# AdjRegSection.net
KiCad netlist of a schematic drawn in Altium Designer
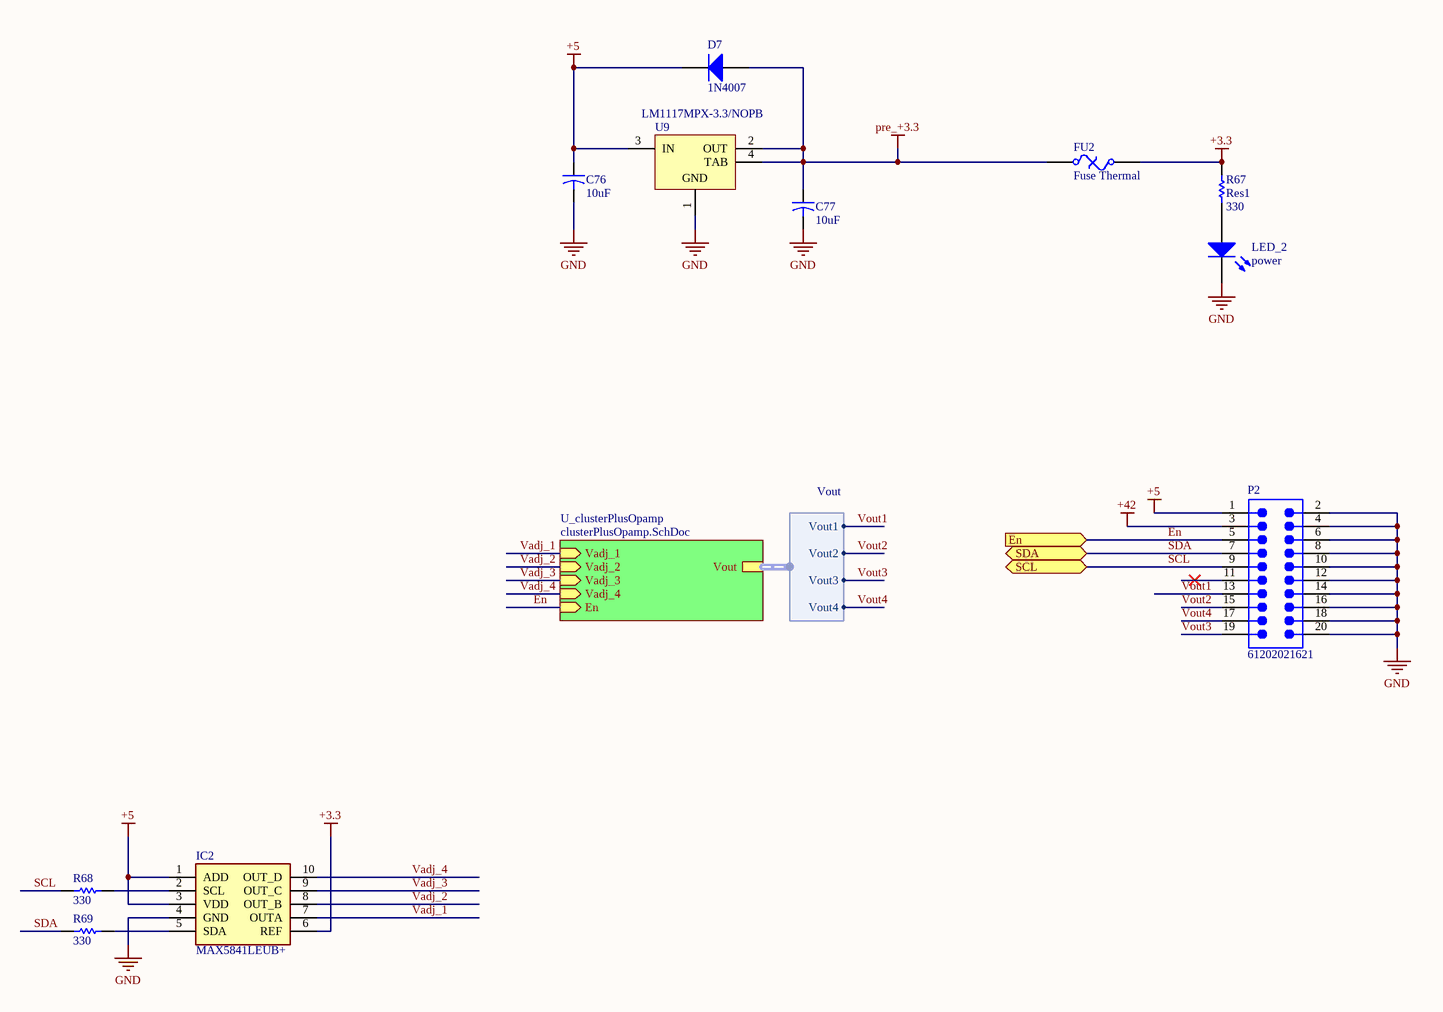
[diagram p0: AdjRegSection.SchDoc]

(export (version "E")
  (design (tool "Eeschema 10.0.6"))
  (components
    (comp (ref "C76")
      (value "10uF")
      (footprint "0805C")
      (description "Capacitor")
      (fields (field (name "Comment") "Cap_El") (field (name "PUBLISHER") "Altium Limited"))
      (libsource (lib "KN2CLib") (part "Cap_El"))
    )
    (comp (ref "C77")
      (value "10uF")
      (footprint "0805C")
      (description "Capacitor")
      (fields (field (name "Comment") "Cap_El") (field (name "PUBLISHER") "Altium Limited"))
      (libsource (lib "KN2CLib") (part "Cap_El"))
    )
    (comp (ref "D7")
      (value "1N4007")
      (footprint "430X270D")
      (description "1 Amp General Purpose Rectifier")
      (fields (field (name "PUBLISHER") "Altium Limited"))
      (libsource (lib "KN2CLib") (part "Diode"))
    )
    (comp (ref "FU2")
      (value "Fuse Thermal")
      (footprint "1206")
      (description "Thermal Fuse")
      (fields (field (name "PUBLISHER") "Altium Limited"))
      (libsource (lib "Miscellaneous Devices") (part "Fuse Thermal"))
    )
    (comp (ref "IC2")
      (value "MAX5841LEUB+")
      (footprint "SamacSys:SOP50P490X110-10N")
      (description "Integrated Circuit")
      (fields (field (name "MOUSER PART NUMBER") "700-MAX5841LEUB"))
      (libsource (lib "*") (part "MAX5841LEUB+"))
    )
    (comp (ref "LED_2")
      (value "power")
      (footprint "0805LED")
      (description "Typical BLUE SiC LED")
      (fields (field (name "PUBLISHER") "Altium Limited"))
      (libsource (lib "Miscellaneous Devices") (part "LED3"))
    )
    (comp (ref "P2")
      (value "61202021621")
      (footprint "61202021621")
      (libsource (lib "Altium Content Vault") (part "Header_Male_2R_20P"))
    )
    (comp (ref "R67")
      (value "Res1")
      (footprint "0805L")
      (description "Resistor")
      (fields (field (name "ALTIUM_VALUE") "330") (field (name "PUBLISHER") "Altium Limited"))
      (libsource (lib "Miscellaneous Devices") (part "Res1"))
    )
    (comp (ref "R68")
      (value "330")
      (footprint "RESC3216X70X50NL05T20")
      (fields (field (name "PART NUMBER") "ERJ8BWFR068V") (field (name "MANUFACTURER") "Panasonic"))
      (libsource (lib "Altium Content Vault") (part "RES"))
    )
    (comp (ref "R69")
      (value "330")
      (footprint "RESC3216X70X50NL05T20")
      (fields (field (name "PART NUMBER") "ERJ8BWFR068V") (field (name "MANUFACTURER") "Panasonic"))
      (libsource (lib "Altium Content Vault") (part "RES"))
    )
    (comp (ref "U9")
      (value "LM1117MPX-3.3/NOPB")
      (footprint "DCY0004A_L")
      (description "800mA Low-Dropout Linear Regulator, 4-pin SOT-223, Pb-Free")
      (fields (field (name "MANUFACTURER") "Texas Instruments"))
      (libsource (lib "Altium Content Vault") (part "PM-REG-LM1086-SOT4"))
    )
  )
  (nets
    (net (code "2") (name "+3.3") (class "Default")
      (node (ref "FU2") (pin "2") (pinfunction "2_2") (pintype "passive"))
      (node (ref "IC2") (pin "6") (pinfunction "REF_6") (pintype "passive"))
      (node (ref "R67") (pin "1") (pinfunction "1_1") (pintype "passive"))
    )
    (net (code "3") (name "+5") (class "Default")
      (node (ref "C76") (pin "1") (pinfunction "1_1") (pintype "passive"))
      (node (ref "D7") (pin "2") (pinfunction "K_2") (pintype "passive"))
      (node (ref "IC2") (pin "1") (pinfunction "ADD_1") (pintype "passive"))
      (node (ref "IC2") (pin "3") (pinfunction "VDD_3") (pintype "passive"))
      (node (ref "P2") (pin "1") (pinfunction "1_1") (pintype "passive"))
      (node (ref "U9") (pin "3") (pinfunction "IN_3") (pintype "power_in"))
    )
    (net (code "4") (name "+42") (class "Default")
      (node (ref "P2") (pin "3") (pinfunction "3_3") (pintype "passive"))
    )
    (net (code "5") (name "/En") (class "Default")
      (node (ref "P2") (pin "5") (pinfunction "5_5") (pintype "passive"))
    )
    (net (code "6") (name "/SCL") (class "Default")
      (node (ref "P2") (pin "9") (pinfunction "9_9") (pintype "passive"))
      (node (ref "R68") (pin "2") (pinfunction "2_2") (pintype "passive"))
    )
    (net (code "7") (name "/SDA") (class "Default")
      (node (ref "P2") (pin "7") (pinfunction "7_7") (pintype "passive"))
      (node (ref "R69") (pin "2") (pinfunction "2_2") (pintype "passive"))
    )
    (net (code "8") (name "/Vadj_1") (class "Default")
      (node (ref "IC2") (pin "7") (pinfunction "OUTA_7") (pintype "passive"))
    )
    (net (code "9") (name "/Vadj_2") (class "Default")
      (node (ref "IC2") (pin "8") (pinfunction "OUT_B_8") (pintype "passive"))
    )
    (net (code "10") (name "/Vadj_3") (class "Default")
      (node (ref "IC2") (pin "9") (pinfunction "OUT_C_9") (pintype "passive"))
    )
    (net (code "11") (name "/Vadj_4") (class "Default")
      (node (ref "IC2") (pin "10") (pinfunction "OUT_D_10") (pintype "passive"))
    )
    (net (code "12") (name "/Vout1") (class "Default")
      (node (ref "P2") (pin "13") (pinfunction "13_13") (pintype "passive"))
    )
    (net (code "13") (name "/Vout2") (class "Default")
      (node (ref "P2") (pin "15") (pinfunction "15_15") (pintype "passive"))
    )
    (net (code "14") (name "/Vout3") (class "Default")
      (node (ref "P2") (pin "19") (pinfunction "19_19") (pintype "passive"))
    )
    (net (code "15") (name "/Vout4") (class "Default")
      (node (ref "P2") (pin "17") (pinfunction "17_17") (pintype "passive"))
    )
    (net (code "17") (name "GND") (class "Default")
      (node (ref "C76") (pin "2") (pinfunction "2_2") (pintype "passive"))
      (node (ref "C77") (pin "2") (pinfunction "2_2") (pintype "passive"))
      (node (ref "IC2") (pin "4") (pinfunction "GND_4") (pintype "passive"))
      (node (ref "LED_2") (pin "2") (pinfunction "K_2") (pintype "passive"))
      (node (ref "P2") (pin "10") (pinfunction "10_10") (pintype "passive"))
      (node (ref "P2") (pin "12") (pinfunction "12_12") (pintype "passive"))
      (node (ref "P2") (pin "14") (pinfunction "14_14") (pintype "passive"))
      (node (ref "P2") (pin "16") (pinfunction "16_16") (pintype "passive"))
      (node (ref "P2") (pin "18") (pinfunction "18_18") (pintype "passive"))
      (node (ref "P2") (pin "2") (pinfunction "2_2") (pintype "passive"))
      (node (ref "P2") (pin "20") (pinfunction "20_20") (pintype "passive"))
      (node (ref "P2") (pin "4") (pinfunction "4_4") (pintype "passive"))
      (node (ref "P2") (pin "6") (pinfunction "6_6") (pintype "passive"))
      (node (ref "P2") (pin "8") (pinfunction "8_8") (pintype "passive"))
      (node (ref "U9") (pin "1") (pinfunction "GND_1") (pintype "power_in"))
    )
    (net (code "18") (name "Net-(IC2-SCL)") (class "Default")
      (node (ref "IC2") (pin "2") (pinfunction "SCL_2") (pintype "passive"))
      (node (ref "R68") (pin "1") (pinfunction "1_1") (pintype "passive"))
    )
    (net (code "19") (name "Net-(IC2-SDA)") (class "Default")
      (node (ref "IC2") (pin "5") (pinfunction "SDA_5") (pintype "passive"))
      (node (ref "R69") (pin "1") (pinfunction "1_1") (pintype "passive"))
    )
    (net (code "20") (name "Net-(LED_2-A)") (class "Default")
      (node (ref "LED_2") (pin "1") (pinfunction "A_1") (pintype "passive"))
      (node (ref "R67") (pin "2") (pinfunction "2_2") (pintype "passive"))
    )
    (net (code "21") (name "pre_+3.3") (class "Default")
      (node (ref "C77") (pin "1") (pinfunction "1_1") (pintype "passive"))
      (node (ref "D7") (pin "1") (pinfunction "A_1") (pintype "passive"))
      (node (ref "FU2") (pin "1") (pinfunction "1_1") (pintype "passive"))
      (node (ref "U9") (pin "2") (pinfunction "OUT_2") (pintype "power_in"))
      (node (ref "U9") (pin "4") (pinfunction "TAB_4") (pintype "power_in"))
    )
    (net (code "22") (name "unconnected-(P2-Pad11)") (class "Default")
      (node (ref "P2") (pin "11") (pinfunction "11_11") (pintype "passive"))
    )
  )
)
